# DinoCalc_1v0.net
KiCad netlist of a schematic drawn in EAGLE
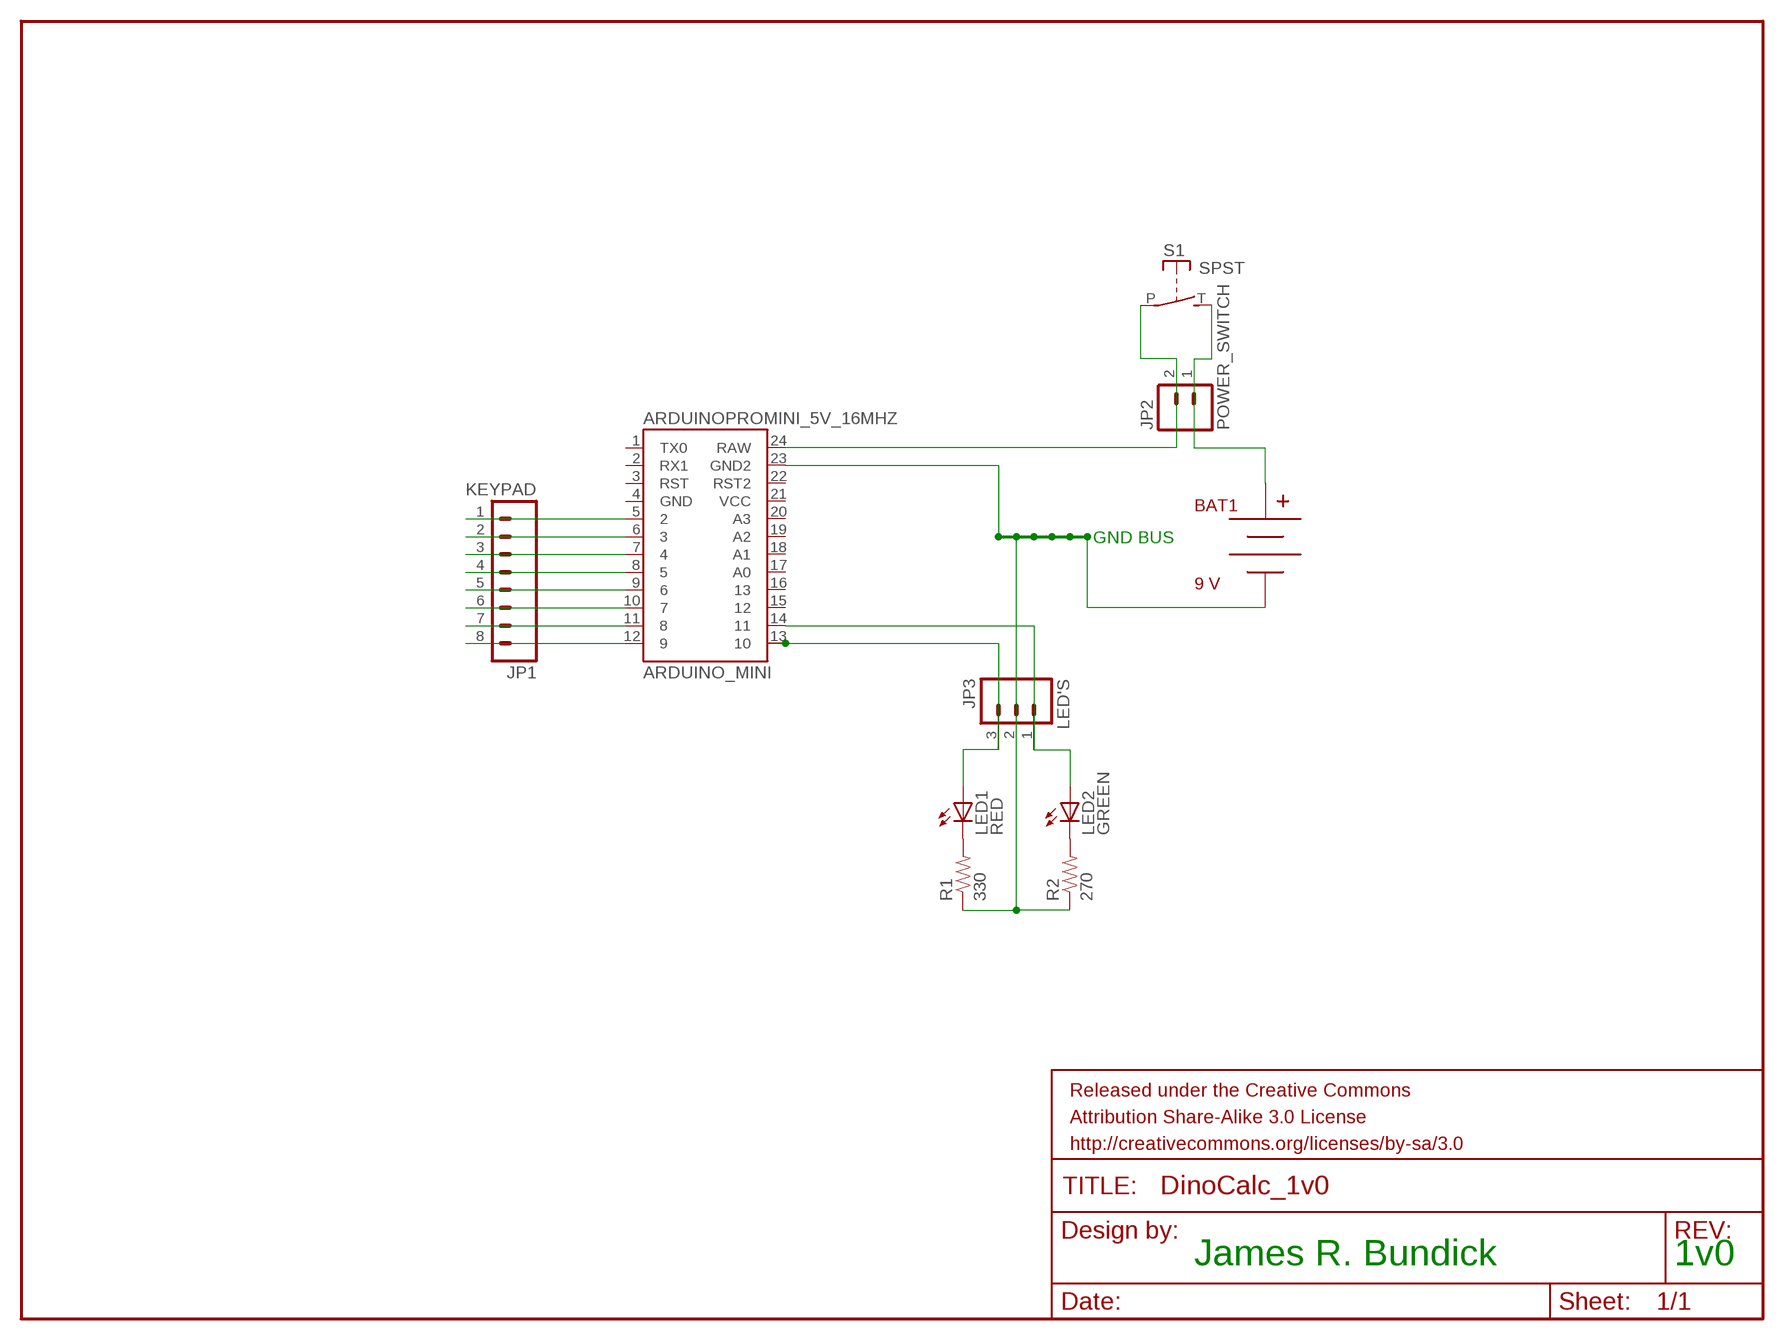
[diagram p0: schematic, sheet 1]

(export (version "E")
  (design (tool "Eeschema 10.0.6"))
  (components
    (comp (ref "ARDUINOPROMINI_5V_16MHZ")
      (value "ARDUINO_MINI")
      (footprint "eagle-import:ARDUINO_MINI")
      (libsource (lib "eagle-import") (part "ARDUINO_MINI"))
    )
    (comp (ref "BAT1")
      (value "9 V")
      (footprint "eagle-import:BC9VPC")
      (libsource (lib "eagle-import") (part "BC9VPC"))
    )
    (comp (ref "FRAME1")
      (value "FRAME-LETTER")
      (footprint "eagle-import:CREATIVE_COMMONS")
      (libsource (lib "eagle-import") (part "FRAME-LETTER"))
    )
    (comp (ref "JP1")
      (value "KEYPAD")
      (footprint "eagle-import:1X08_LONGPADS")
      (libsource (lib "eagle-import") (part "M08LONGPADS"))
    )
    (comp (ref "JP2")
      (value "POWER_SWITCH")
      (footprint "eagle-import:1X02_LONGPADS")
      (libsource (lib "eagle-import") (part "M02PTH3"))
    )
    (comp (ref "JP3")
      (value "LED'S")
      (footprint "eagle-import:1X03_LONGPADS")
      (libsource (lib "eagle-import") (part "M03LONGPADS"))
    )
    (comp (ref "LED1")
      (value "RED")
      (footprint "eagle-import:LED5MM")
      (libsource (lib "eagle-import") (part "LED5MM"))
    )
    (comp (ref "LED2")
      (value "GREEN")
      (footprint "eagle-import:LED5MM")
      (libsource (lib "eagle-import") (part "LED5MM"))
    )
    (comp (ref "R1")
      (value "330")
      (footprint "eagle-import:AXIAL-0.4")
      (libsource (lib "eagle-import") (part "RESISTORPTH-1/4W"))
    )
    (comp (ref "R2")
      (value "270")
      (footprint "eagle-import:AXIAL-0.4")
      (libsource (lib "eagle-import") (part "RESISTORPTH-1/4W"))
    )
    (comp (ref "S1")
      (value "SPST")
      (footprint "eagle-import:JUDCOSPST")
      (libsource (lib "eagle-import") (part "SPST"))
    )
  )
  (nets
    (net (code "1") (name "Net-(ARDUINOPROMINI_5V_16MHZ-2)") (class "Default")
      (node (ref "ARDUINOPROMINI_5V_16MHZ") (pin "5") (pinfunction "2_5") (pintype "bidirectional"))
      (node (ref "JP1") (pin "1") (pinfunction "1_1") (pintype "passive"))
    )
    (net (code "2") (name "Net-(ARDUINOPROMINI_5V_16MHZ-3)") (class "Default")
      (node (ref "ARDUINOPROMINI_5V_16MHZ") (pin "6") (pinfunction "3_6") (pintype "bidirectional"))
      (node (ref "JP1") (pin "2") (pinfunction "2_2") (pintype "passive"))
    )
    (net (code "3") (name "Net-(ARDUINOPROMINI_5V_16MHZ-4)") (class "Default")
      (node (ref "ARDUINOPROMINI_5V_16MHZ") (pin "7") (pinfunction "4_7") (pintype "bidirectional"))
      (node (ref "JP1") (pin "3") (pinfunction "3_3") (pintype "passive"))
    )
    (net (code "4") (name "Net-(ARDUINOPROMINI_5V_16MHZ-5)") (class "Default")
      (node (ref "ARDUINOPROMINI_5V_16MHZ") (pin "8") (pinfunction "5_8") (pintype "bidirectional"))
      (node (ref "JP1") (pin "4") (pinfunction "4_4") (pintype "passive"))
    )
    (net (code "5") (name "Net-(ARDUINOPROMINI_5V_16MHZ-6)") (class "Default")
      (node (ref "ARDUINOPROMINI_5V_16MHZ") (pin "9") (pinfunction "6_9") (pintype "bidirectional"))
      (node (ref "JP1") (pin "5") (pinfunction "5_5") (pintype "passive"))
    )
    (net (code "6") (name "Net-(ARDUINOPROMINI_5V_16MHZ-7)") (class "Default")
      (node (ref "ARDUINOPROMINI_5V_16MHZ") (pin "10") (pinfunction "7_10") (pintype "bidirectional"))
      (node (ref "JP1") (pin "6") (pinfunction "6_6") (pintype "passive"))
    )
    (net (code "7") (name "Net-(ARDUINOPROMINI_5V_16MHZ-8)") (class "Default")
      (node (ref "ARDUINOPROMINI_5V_16MHZ") (pin "11") (pinfunction "8_11") (pintype "bidirectional"))
      (node (ref "JP1") (pin "7") (pinfunction "7_7") (pintype "passive"))
    )
    (net (code "8") (name "Net-(ARDUINOPROMINI_5V_16MHZ-9)") (class "Default")
      (node (ref "ARDUINOPROMINI_5V_16MHZ") (pin "12") (pinfunction "9_12") (pintype "bidirectional"))
      (node (ref "JP1") (pin "8") (pinfunction "8_8") (pintype "passive"))
    )
    (net (code "9") (name "Net-(ARDUINOPROMINI_5V_16MHZ-10)") (class "Default")
      (node (ref "ARDUINOPROMINI_5V_16MHZ") (pin "13") (pinfunction "10_13") (pintype "bidirectional"))
      (node (ref "JP3") (pin "3") (pinfunction "3_3") (pintype "passive"))
      (node (ref "LED1") (pin "A") (pinfunction "A_A") (pintype "passive"))
    )
    (net (code "10") (name "Net-(ARDUINOPROMINI_5V_16MHZ-11)") (class "Default")
      (node (ref "ARDUINOPROMINI_5V_16MHZ") (pin "14") (pinfunction "11_14") (pintype "bidirectional"))
      (node (ref "JP3") (pin "1") (pinfunction "1_1") (pintype "passive"))
      (node (ref "LED2") (pin "A") (pinfunction "A_A") (pintype "passive"))
    )
    (net (code "11") (name "Net-(ARDUINOPROMINI_5V_16MHZ-GND2)") (class "Default")
      (node (ref "ARDUINOPROMINI_5V_16MHZ") (pin "23") (pinfunction "GND2_23") (pintype "bidirectional"))
      (node (ref "BAT1") (pin "V-") (pinfunction "V-_V-") (pintype "bidirectional"))
      (node (ref "JP3") (pin "2") (pinfunction "2_2") (pintype "passive"))
      (node (ref "R1") (pin "P$1") (pinfunction "1_P$1") (pintype "passive"))
      (node (ref "R2") (pin "P$1") (pinfunction "1_P$1") (pintype "passive"))
    )
    (net (code "12") (name "Net-(ARDUINOPROMINI_5V_16MHZ-RAW)") (class "Default")
      (node (ref "ARDUINOPROMINI_5V_16MHZ") (pin "24") (pinfunction "RAW_24") (pintype "bidirectional"))
      (node (ref "JP2") (pin "2") (pinfunction "2_2") (pintype "passive"))
      (node (ref "S1") (pin "P") (pinfunction "P_P") (pintype "passive"))
    )
    (net (code "13") (name "Net-(LED1-C)") (class "Default")
      (node (ref "LED1") (pin "K") (pinfunction "C_K") (pintype "passive"))
      (node (ref "R1") (pin "P$2") (pinfunction "2_P$2") (pintype "passive"))
    )
    (net (code "14") (name "Net-(LED2-C)") (class "Default")
      (node (ref "LED2") (pin "K") (pinfunction "C_K") (pintype "passive"))
      (node (ref "R2") (pin "P$2") (pinfunction "2_P$2") (pintype "passive"))
    )
    (net (code "15") (name "Net-(S1-S)") (class "Default")
      (node (ref "BAT1") (pin "V+") (pinfunction "V+_V+") (pintype "bidirectional"))
      (node (ref "JP2") (pin "1") (pinfunction "1_1") (pintype "passive"))
      (node (ref "S1") (pin "T") (pinfunction "S_T") (pintype "passive"))
    )
    (net (code "16") (name "unconnected-(ARDUINOPROMINI_5V_16MHZ-12-Pad15)") (class "Default")
      (node (ref "ARDUINOPROMINI_5V_16MHZ") (pin "15") (pinfunction "12_15") (pintype "bidirectional"))
    )
    (net (code "17") (name "unconnected-(ARDUINOPROMINI_5V_16MHZ-13-Pad16)") (class "Default")
      (node (ref "ARDUINOPROMINI_5V_16MHZ") (pin "16") (pinfunction "13_16") (pintype "bidirectional"))
    )
    (net (code "18") (name "unconnected-(ARDUINOPROMINI_5V_16MHZ-A0-Pad17)") (class "Default")
      (node (ref "ARDUINOPROMINI_5V_16MHZ") (pin "17") (pinfunction "A0_17") (pintype "bidirectional"))
    )
    (net (code "19") (name "unconnected-(ARDUINOPROMINI_5V_16MHZ-A1-Pad18)") (class "Default")
      (node (ref "ARDUINOPROMINI_5V_16MHZ") (pin "18") (pinfunction "A1_18") (pintype "bidirectional"))
    )
    (net (code "20") (name "unconnected-(ARDUINOPROMINI_5V_16MHZ-A2-Pad19)") (class "Default")
      (node (ref "ARDUINOPROMINI_5V_16MHZ") (pin "19") (pinfunction "A2_19") (pintype "bidirectional"))
    )
    (net (code "21") (name "unconnected-(ARDUINOPROMINI_5V_16MHZ-A3-Pad20)") (class "Default")
      (node (ref "ARDUINOPROMINI_5V_16MHZ") (pin "20") (pinfunction "A3_20") (pintype "bidirectional"))
    )
    (net (code "22") (name "unconnected-(ARDUINOPROMINI_5V_16MHZ-GND-Pad4)") (class "Default")
      (node (ref "ARDUINOPROMINI_5V_16MHZ") (pin "4") (pinfunction "GND_4") (pintype "bidirectional"))
    )
    (net (code "23") (name "unconnected-(ARDUINOPROMINI_5V_16MHZ-RST-Pad3)") (class "Default")
      (node (ref "ARDUINOPROMINI_5V_16MHZ") (pin "3") (pinfunction "RST_3") (pintype "bidirectional"))
    )
    (net (code "24") (name "unconnected-(ARDUINOPROMINI_5V_16MHZ-RST2-Pad22)") (class "Default")
      (node (ref "ARDUINOPROMINI_5V_16MHZ") (pin "22") (pinfunction "RST2_22") (pintype "bidirectional"))
    )
    (net (code "25") (name "unconnected-(ARDUINOPROMINI_5V_16MHZ-RX1-Pad2)") (class "Default")
      (node (ref "ARDUINOPROMINI_5V_16MHZ") (pin "2") (pinfunction "RX1_2") (pintype "bidirectional"))
    )
    (net (code "26") (name "unconnected-(ARDUINOPROMINI_5V_16MHZ-TX0-Pad1)") (class "Default")
      (node (ref "ARDUINOPROMINI_5V_16MHZ") (pin "1") (pinfunction "TX0_1") (pintype "bidirectional"))
    )
    (net (code "27") (name "unconnected-(ARDUINOPROMINI_5V_16MHZ-VCC-Pad21)") (class "Default")
      (node (ref "ARDUINOPROMINI_5V_16MHZ") (pin "21") (pinfunction "VCC_21") (pintype "bidirectional"))
    )
  )
)
